# Sheet1.net
KiCad netlist of a schematic drawn in Altium Designer
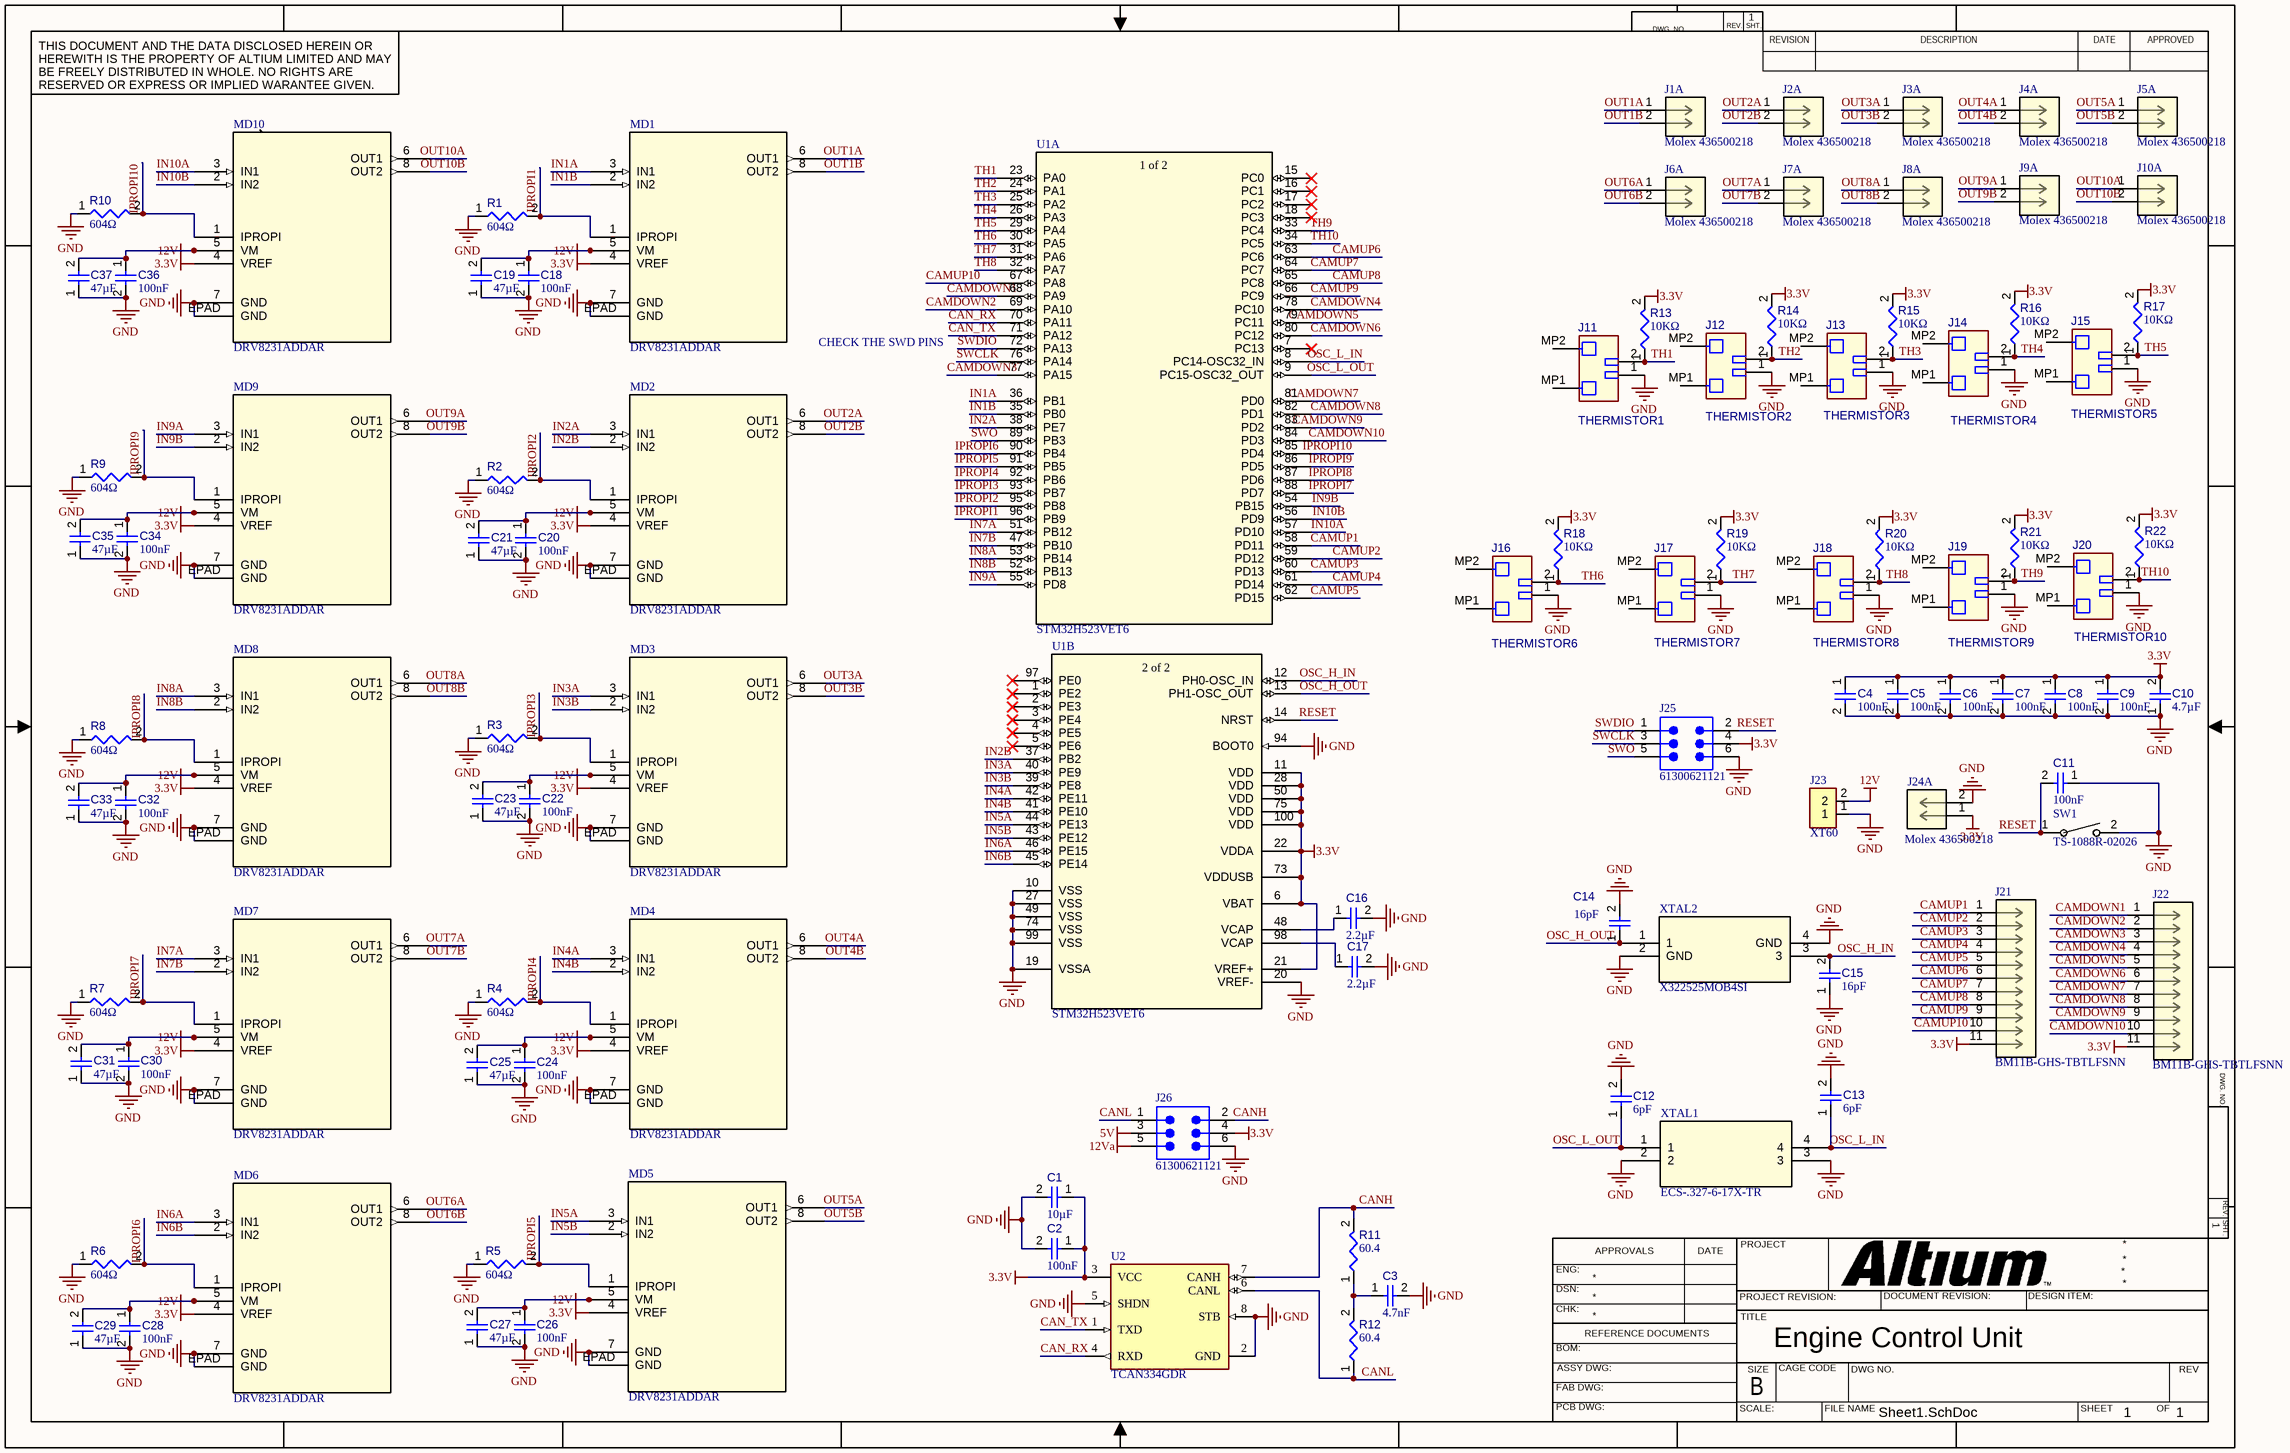
[diagram p0: Sheet1.SchDoc]

(export (version "E")
  (design (tool "Eeschema 10.0.6"))
  (components
    (comp (ref "C1")
      (value "10µF")
      (footprint "CAPC0805(2012)145_L")
      (description "Chip Capacitor, 10µF +/-20%, 25V, 0805, Thickness 1.45 mm")
      (fields (field (name "TOLERANCE") "10%") (field (name "Comment") "Capacitor 10µF +/-20% 25V 0805"))
      (libsource (lib "Caden Chan") (part "CAP-NP-2"))
    )
    (comp (ref "C2")
      (value "100nF")
      (footprint "CAPC0402(1005)60_L")
      (description "Chip Capacitor, 100nF +/-20%, 50V, 0402, Thickness 0.6 mm")
      (fields (field (name "TOLERANCE") "10%") (field (name "Comment") "Capacitor 100nF +/-20% 50V 0402"))
      (libsource (lib "Caden Chan") (part "CAP-NP-2"))
    )
    (comp (ref "C3")
      (value "4.7nF")
      (footprint "CAPC1709X04N")
      (fields (field (name "Comment") "yageo CC0603KRX7R9BB472"))
      (libsource (lib "Caden Chan") (part "CAP-NP-2"))
    )
    (comp (ref "C4")
      (value "100nF")
      (footprint "CAPC0402(1005)60_L")
      (description "Chip Capacitor, 100nF +/-20%, 50V, 0402, Thickness 0.6 mm")
      (fields (field (name "TOLERANCE") "10%") (field (name "Comment") "Capacitor 100nF +/-20% 50V 0402"))
      (libsource (lib "Caden Chan") (part "CAP-NP-2"))
    )
    (comp (ref "C5")
      (value "100nF")
      (footprint "CAPC0402(1005)60_L")
      (description "Chip Capacitor, 100nF +/-20%, 50V, 0402, Thickness 0.6 mm")
      (fields (field (name "TOLERANCE") "10%") (field (name "Comment") "Capacitor 100nF +/-20% 50V 0402"))
      (libsource (lib "Caden Chan") (part "CAP-NP-2"))
    )
    (comp (ref "C6")
      (value "100nF")
      (footprint "CAPC0402(1005)60_L")
      (description "Chip Capacitor, 100nF +/-20%, 50V, 0402, Thickness 0.6 mm")
      (fields (field (name "TOLERANCE") "10%") (field (name "Comment") "Capacitor 100nF +/-20% 50V 0402"))
      (libsource (lib "Caden Chan") (part "CAP-NP-2"))
    )
    (comp (ref "C7")
      (value "100nF")
      (footprint "CAPC0402(1005)60_L")
      (description "Chip Capacitor, 100nF +/-20%, 50V, 0402, Thickness 0.6 mm")
      (fields (field (name "TOLERANCE") "10%") (field (name "Comment") "Capacitor 100nF +/-20% 50V 0402"))
      (libsource (lib "Caden Chan") (part "CAP-NP-2"))
    )
    (comp (ref "C8")
      (value "100nF")
      (footprint "CAPC0402(1005)60_L")
      (description "Chip Capacitor, 100nF +/-20%, 50V, 0402, Thickness 0.6 mm")
      (fields (field (name "TOLERANCE") "10%") (field (name "Comment") "Capacitor 100nF +/-20% 50V 0402"))
      (libsource (lib "Caden Chan") (part "CAP-NP-2"))
    )
    (comp (ref "C9")
      (value "100nF")
      (footprint "CAPC0402(1005)60_L")
      (description "Chip Capacitor, 100nF +/-20%, 50V, 0402, Thickness 0.6 mm")
      (fields (field (name "TOLERANCE") "10%") (field (name "Comment") "Capacitor 100nF +/-20% 50V 0402"))
      (libsource (lib "Caden Chan") (part "CAP-NP-2"))
    )
    (comp (ref "C10")
      (value "4.7µF")
      (footprint "CAPC0603(1608)100_L")
      (description "Chip Capacitor, 4.7µF +/-20%, 10V, 0603, Thickness 1 mm")
      (fields (field (name "TOLERANCE") "10%") (field (name "Comment") "Capacitor 4.7µF +/-20% 10V 0603"))
      (libsource (lib "Caden Chan") (part "CAP-NP-2"))
    )
    (comp (ref "C11")
      (value "100nF")
      (footprint "CAPC0402(1005)60_L")
      (description "Chip Capacitor, 100nF +/-20%, 50V, 0402, Thickness 0.6 mm")
      (fields (field (name "TOLERANCE") "10%") (field (name "Comment") "Capacitor 100nF +/-20% 50V 0402"))
      (libsource (lib "Caden Chan") (part "CAP-NP-2"))
    )
    (comp (ref "C12")
      (value "6pF")
      (footprint "CAPC1709X04N")
      (fields (field (name "Comment") "Yageo CC0603CRNPO9BN6R0"))
      (libsource (lib "Caden Chan") (part "CAP-NP-2"))
    )
    (comp (ref "C13")
      (value "6pF")
      (footprint "CAPC1709X04N")
      (fields (field (name "Comment") "Yageo CC0603CRNPO9BN6R0"))
      (libsource (lib "Caden Chan") (part "CAP-NP-2"))
    )
    (comp (ref "C14")
      (value "16pF")
      (footprint "CAPC1709X04N")
      (description "Multilayer Ceramic Capacitor, 16 pF, 50 V, ± 5%, C0G (NP0), 0603 [1608 Metric]")
      (fields (field (name "Comment") "Yageo CC0603JRNPO9BN160"))
      (libsource (lib "Caden Chan") (part "CAP-NP-2"))
    )
    (comp (ref "C15")
      (value "16pF")
      (footprint "CAPC1709X04N")
      (description "Multilayer Ceramic Capacitor, 16 pF, 50 V, ± 5%, C0G (NP0), 0603 [1608 Metric]")
      (fields (field (name "Comment") "Yageo CC0603JRNPO9BN160"))
      (libsource (lib "Caden Chan") (part "CAP-NP-2"))
    )
    (comp (ref "C16")
      (value "2.2µF")
      (footprint "CAPC1709X04N")
      (fields (field (name "Comment") "yageo CC0603KRX5R8BB225"))
      (libsource (lib "Caden Chan") (part "CAP-NP-2"))
    )
    (comp (ref "C17")
      (value "2.2µF")
      (footprint "CAPC1709X04N")
      (fields (field (name "Comment") "yageo CC0603KRX5R8BB225"))
      (libsource (lib "Caden Chan") (part "CAP-NP-2"))
    )
    (comp (ref "C18")
      (value "100nF")
      (footprint "CAPC0402(1005)60_L")
      (description "Chip Capacitor, 100nF +/-20%, 50V, 0402, Thickness 0.6 mm")
      (fields (field (name "TOLERANCE") "10%") (field (name "Comment") "Capacitor 100nF +/-20% 50V 0402"))
      (libsource (lib "Caden Chan") (part "CAP-NP-2"))
    )
    (comp (ref "C19")
      (value "47µF")
      (footprint "N18F1D473MQ0T0S0N0-Footprint-1")
      (description "±20% 47nF Y5V 1kV Plugin, P=10mm Through Hole Ceramic Capacitors ROHS")
      (fields (field (name "Comment") "N18F1D473MQ0T0S0N0"))
      (libsource (lib "Caden Chan") (part "CAP-NP-2"))
    )
    (comp (ref "C20")
      (value "100nF")
      (footprint "CAPC0402(1005)60_L")
      (description "Chip Capacitor, 100nF +/-20%, 50V, 0402, Thickness 0.6 mm")
      (fields (field (name "TOLERANCE") "10%") (field (name "Comment") "Capacitor 100nF +/-20% 50V 0402"))
      (libsource (lib "Caden Chan") (part "CAP-NP-2"))
    )
    (comp (ref "C21")
      (value "47µF")
      (footprint "N18F1D473MQ0T0S0N0-Footprint-1")
      (description "±20% 47nF Y5V 1kV Plugin, P=10mm Through Hole Ceramic Capacitors ROHS")
      (fields (field (name "Comment") "N18F1D473MQ0T0S0N0"))
      (libsource (lib "Caden Chan") (part "CAP-NP-2"))
    )
    (comp (ref "C22")
      (value "100nF")
      (footprint "CAPC0402(1005)60_L")
      (description "Chip Capacitor, 100nF +/-20%, 50V, 0402, Thickness 0.6 mm")
      (fields (field (name "TOLERANCE") "10%") (field (name "Comment") "Capacitor 100nF +/-20% 50V 0402"))
      (libsource (lib "Caden Chan") (part "CAP-NP-2"))
    )
    (comp (ref "C23")
      (value "47µF")
      (footprint "N18F1D473MQ0T0S0N0-Footprint-1")
      (description "±20% 47nF Y5V 1kV Plugin, P=10mm Through Hole Ceramic Capacitors ROHS")
      (fields (field (name "Comment") "N18F1D473MQ0T0S0N0"))
      (libsource (lib "Caden Chan") (part "CAP-NP-2"))
    )
    (comp (ref "C24")
      (value "100nF")
      (footprint "CAPC0402(1005)60_L")
      (description "Chip Capacitor, 100nF +/-20%, 50V, 0402, Thickness 0.6 mm")
      (fields (field (name "TOLERANCE") "10%") (field (name "Comment") "Capacitor 100nF +/-20% 50V 0402"))
      (libsource (lib "Caden Chan") (part "CAP-NP-2"))
    )
    (comp (ref "C25")
      (value "47µF")
      (footprint "N18F1D473MQ0T0S0N0-Footprint-1")
      (description "±20% 47nF Y5V 1kV Plugin, P=10mm Through Hole Ceramic Capacitors ROHS")
      (fields (field (name "Comment") "N18F1D473MQ0T0S0N0"))
      (libsource (lib "Caden Chan") (part "CAP-NP-2"))
    )
    (comp (ref "C26")
      (value "100nF")
      (footprint "CAPC0402(1005)60_L")
      (description "Chip Capacitor, 100nF +/-20%, 50V, 0402, Thickness 0.6 mm")
      (fields (field (name "TOLERANCE") "10%") (field (name "Comment") "Capacitor 100nF +/-20% 50V 0402"))
      (libsource (lib "Caden Chan") (part "CAP-NP-2"))
    )
    (comp (ref "C27")
      (value "47µF")
      (footprint "N18F1D473MQ0T0S0N0-Footprint-1")
      (description "±20% 47nF Y5V 1kV Plugin, P=10mm Through Hole Ceramic Capacitors ROHS")
      (fields (field (name "Comment") "N18F1D473MQ0T0S0N0"))
      (libsource (lib "Caden Chan") (part "CAP-NP-2"))
    )
    (comp (ref "C28")
      (value "100nF")
      (footprint "CAPC0402(1005)60_L")
      (description "Chip Capacitor, 100nF +/-20%, 50V, 0402, Thickness 0.6 mm")
      (fields (field (name "TOLERANCE") "10%") (field (name "Comment") "Capacitor 100nF +/-20% 50V 0402"))
      (libsource (lib "Caden Chan") (part "CAP-NP-2"))
    )
    (comp (ref "C29")
      (value "47µF")
      (footprint "N18F1D473MQ0T0S0N0-Footprint-1")
      (description "±20% 47nF Y5V 1kV Plugin, P=10mm Through Hole Ceramic Capacitors ROHS")
      (fields (field (name "Comment") "N18F1D473MQ0T0S0N0"))
      (libsource (lib "Caden Chan") (part "CAP-NP-2"))
    )
    (comp (ref "C30")
      (value "100nF")
      (footprint "CAPC0402(1005)60_L")
      (description "Chip Capacitor, 100nF +/-20%, 50V, 0402, Thickness 0.6 mm")
      (fields (field (name "TOLERANCE") "10%") (field (name "Comment") "Capacitor 100nF +/-20% 50V 0402"))
      (libsource (lib "Caden Chan") (part "CAP-NP-2"))
    )
    (comp (ref "C31")
      (value "47µF")
      (footprint "N18F1D473MQ0T0S0N0-Footprint-1")
      (description "±20% 47nF Y5V 1kV Plugin, P=10mm Through Hole Ceramic Capacitors ROHS")
      (fields (field (name "Comment") "N18F1D473MQ0T0S0N0"))
      (libsource (lib "Caden Chan") (part "CAP-NP-2"))
    )
    (comp (ref "C32")
      (value "100nF")
      (footprint "CAPC0402(1005)60_L")
      (description "Chip Capacitor, 100nF +/-20%, 50V, 0402, Thickness 0.6 mm")
      (fields (field (name "TOLERANCE") "10%") (field (name "Comment") "Capacitor 100nF +/-20% 50V 0402"))
      (libsource (lib "Caden Chan") (part "CAP-NP-2"))
    )
    (comp (ref "C33")
      (value "47µF")
      (footprint "N18F1D473MQ0T0S0N0-Footprint-1")
      (description "±20% 47nF Y5V 1kV Plugin, P=10mm Through Hole Ceramic Capacitors ROHS")
      (fields (field (name "Comment") "N18F1D473MQ0T0S0N0"))
      (libsource (lib "Caden Chan") (part "CAP-NP-2"))
    )
    (comp (ref "C34")
      (value "100nF")
      (footprint "CAPC0402(1005)60_L")
      (description "Chip Capacitor, 100nF +/-20%, 50V, 0402, Thickness 0.6 mm")
      (fields (field (name "TOLERANCE") "10%") (field (name "Comment") "Capacitor 100nF +/-20% 50V 0402"))
      (libsource (lib "Caden Chan") (part "CAP-NP-2"))
    )
    (comp (ref "C35")
      (value "47µF")
      (footprint "N18F1D473MQ0T0S0N0-Footprint-1")
      (description "±20% 47nF Y5V 1kV Plugin, P=10mm Through Hole Ceramic Capacitors ROHS")
      (fields (field (name "Comment") "N18F1D473MQ0T0S0N0"))
      (libsource (lib "Caden Chan") (part "CAP-NP-2"))
    )
    (comp (ref "C36")
      (value "100nF")
      (footprint "CAPC0402(1005)60_L")
      (description "Chip Capacitor, 100nF +/-20%, 50V, 0402, Thickness 0.6 mm")
      (fields (field (name "TOLERANCE") "10%") (field (name "Comment") "Capacitor 100nF +/-20% 50V 0402"))
      (libsource (lib "Caden Chan") (part "CAP-NP-2"))
    )
    (comp (ref "C37")
      (value "47µF")
      (footprint "N18F1D473MQ0T0S0N0-Footprint-1")
      (description "±20% 47nF Y5V 1kV Plugin, P=10mm Through Hole Ceramic Capacitors ROHS")
      (fields (field (name "Comment") "N18F1D473MQ0T0S0N0"))
      (libsource (lib "Caden Chan") (part "CAP-NP-2"))
    )
    (comp (ref "J1")
      (value "Molex 436500218")
      (footprint "CONN_SD-43650-007_02_MOL")
      (description "No Description Available")
      (libsource (lib "") (part "436500218_1"))
    )
    (comp (ref "J2")
      (value "Molex 436500218")
      (footprint "CONN_SD-43650-007_02_MOL")
      (description "No Description Available")
      (libsource (lib "") (part "436500218_1"))
    )
    (comp (ref "J3")
      (value "Molex 436500218")
      (footprint "CONN_SD-43650-007_02_MOL")
      (description "No Description Available")
      (libsource (lib "") (part "436500218_1"))
    )
    (comp (ref "J4")
      (value "Molex 436500218")
      (footprint "CONN_SD-43650-007_02_MOL")
      (description "No Description Available")
      (libsource (lib "") (part "436500218_1"))
    )
    (comp (ref "J5")
      (value "Molex 436500218")
      (footprint "CONN_SD-43650-007_02_MOL")
      (description "No Description Available")
      (libsource (lib "") (part "436500218_1"))
    )
    (comp (ref "J6")
      (value "Molex 436500218")
      (footprint "CONN_SD-43650-007_02_MOL")
      (description "No Description Available")
      (libsource (lib "") (part "436500218_1"))
    )
    (comp (ref "J7")
      (value "Molex 436500218")
      (footprint "CONN_SD-43650-007_02_MOL")
      (description "No Description Available")
      (libsource (lib "") (part "436500218_1"))
    )
    (comp (ref "J8")
      (value "Molex 436500218")
      (footprint "CONN_SD-43650-007_02_MOL")
      (description "No Description Available")
      (libsource (lib "") (part "436500218_1"))
    )
    (comp (ref "J9")
      (value "Molex 436500218")
      (footprint "CONN_SD-43650-007_02_MOL")
      (description "No Description Available")
      (libsource (lib "") (part "436500218_1"))
    )
    (comp (ref "J10")
      (value "Molex 436500218")
      (footprint "CONN_SD-43650-007_02_MOL")
      (description "No Description Available")
      (libsource (lib "") (part "436500218_1"))
    )
    (comp (ref "J11")
      (value "THERMISTOR1")
      (footprint "JST-BM02B-GHS-TBT_V")
      (libsource (lib "Caden Chan") (part "CMP-00144-3"))
    )
    (comp (ref "J12")
      (value "THERMISTOR2")
      (footprint "JST-BM02B-GHS-TBT_V")
      (libsource (lib "Caden Chan") (part "CMP-00144-3"))
    )
    (comp (ref "J13")
      (value "THERMISTOR3")
      (footprint "JST-BM02B-GHS-TBT_V")
      (libsource (lib "Caden Chan") (part "CMP-00144-3"))
    )
    (comp (ref "J14")
      (value "THERMISTOR4")
      (footprint "JST-BM02B-GHS-TBT_V")
      (libsource (lib "Caden Chan") (part "CMP-00144-3"))
    )
    (comp (ref "J15")
      (value "THERMISTOR5")
      (footprint "JST-BM02B-GHS-TBT_V")
      (libsource (lib "Caden Chan") (part "CMP-00144-3"))
    )
    (comp (ref "J16")
      (value "THERMISTOR6")
      (footprint "JST-BM02B-GHS-TBT_V")
      (libsource (lib "Caden Chan") (part "CMP-00144-3"))
    )
    (comp (ref "J17")
      (value "THERMISTOR7")
      (footprint "JST-BM02B-GHS-TBT_V")
      (libsource (lib "Caden Chan") (part "CMP-00144-3"))
    )
    (comp (ref "J18")
      (value "THERMISTOR8")
      (footprint "JST-BM02B-GHS-TBT_V")
      (libsource (lib "Caden Chan") (part "CMP-00144-3"))
    )
    (comp (ref "J19")
      (value "THERMISTOR9")
      (footprint "JST-BM02B-GHS-TBT_V")
      (libsource (lib "Caden Chan") (part "CMP-00144-3"))
    )
    (comp (ref "J20")
      (value "THERMISTOR10")
      (footprint "JST-BM02B-GHS-TBT_V")
      (libsource (lib "Caden Chan") (part "CMP-00144-3"))
    )
    (comp (ref "J21")
      (value "BM11B-GHS-TBTLFSNN")
      (footprint "CONN11_BM11B-GHS-TBTLFSNN_JST")
      (description "No Description Available")
      (fields
        (field (name "MANUFACTURER_PART_NUMBER") "BM11B-GHS-TBT(LF)(SN)(N)")
        (field (name "COPYRIGHT") "Copyright (C) 2025 Ultra Librarian. All rights reserved.")
      )
      (libsource (lib "Caden Chan") (part "BM11B-GHS-TBTLFSNN"))
    )
    (comp (ref "J22")
      (value "BM11B-GHS-TBTLFSNN")
      (footprint "CONN11_BM11B-GHS-TBTLFSNN_JST")
      (description "No Description Available")
      (fields
        (field (name "MANUFACTURER_PART_NUMBER") "BM11B-GHS-TBT(LF)(SN)(N)")
        (field (name "COPYRIGHT") "Copyright (C) 2025 Ultra Librarian. All rights reserved.")
      )
      (libsource (lib "Caden Chan") (part "BM11B-GHS-TBTLFSNN"))
    )
    (comp (ref "J23")
      (value "XT60")
      (footprint "AMASS_XT60PB-M")
      (description "Power connector; 65A; PIN: 2; Colour: yellow")
      (fields (field (name "MF") "Pololu") (field (name "MP") "XT60 YELLOW"))
      (libsource (lib "Caden Chan") (part "XT60_YELLOW"))
    )
    (comp (ref "J24")
      (value "Molex 436500218")
      (footprint "CONN_SD-43650-007_02_MOL")
      (description "No Description Available")
      (libsource (lib "Caden Chan") (part "436500218"))
    )
    (comp (ref "J25")
      (value "61300621121")
      (footprint "61300621121")
      (description "WR-PHD Pin Header, THT, Vertical, pitch 2.54mm, 2 Row, 6P")
      (fields (field (name "MANUFACTURER") "Wurth Elektronik"))
      (libsource (lib "Caden Chan") (part "61300621121"))
    )
    (comp (ref "J26")
      (value "61300621121")
      (footprint "61300621121")
      (description "WR-PHD Pin Header, THT, Vertical, pitch 2.54mm, 2 Row, 6P")
      (fields (field (name "MANUFACTURER") "Wurth Elektronik"))
      (libsource (lib "Caden Chan") (part "61300621121"))
    )
    (comp (ref "MD1")
      (value "DRV8231ADDAR")
      (footprint "SOIC-8-DDA-DRV8231_TEX")
      (description "No Description Available")
      (libsource (lib "Caden Chan") (part "DRV8231ADDAR"))
    )
    (comp (ref "MD2")
      (value "DRV8231ADDAR")
      (footprint "SOIC-8-DDA-DRV8231_TEX")
      (description "No Description Available")
      (libsource (lib "Caden Chan") (part "DRV8231ADDAR"))
    )
    (comp (ref "MD3")
      (value "DRV8231ADDAR")
      (footprint "SOIC-8-DDA-DRV8231_TEX")
      (description "No Description Available")
      (libsource (lib "Caden Chan") (part "DRV8231ADDAR"))
    )
    (comp (ref "MD4")
      (value "DRV8231ADDAR")
      (footprint "SOIC-8-DDA-DRV8231_TEX")
      (description "No Description Available")
      (libsource (lib "Caden Chan") (part "DRV8231ADDAR"))
    )
    (comp (ref "MD5")
      (value "DRV8231ADDAR")
      (footprint "SOIC-8-DDA-DRV8231_TEX")
      (description "No Description Available")
      (libsource (lib "Caden Chan") (part "DRV8231ADDAR"))
    )
    (comp (ref "MD6")
      (value "DRV8231ADDAR")
      (footprint "SOIC-8-DDA-DRV8231_TEX")
      (description "No Description Available")
      (libsource (lib "Caden Chan") (part "DRV8231ADDAR"))
    )
    (comp (ref "MD7")
      (value "DRV8231ADDAR")
      (footprint "SOIC-8-DDA-DRV8231_TEX")
      (description "No Description Available")
      (libsource (lib "Caden Chan") (part "DRV8231ADDAR"))
    )
    (comp (ref "MD8")
      (value "DRV8231ADDAR")
      (footprint "SOIC-8-DDA-DRV8231_TEX")
      (description "No Description Available")
      (libsource (lib "Caden Chan") (part "DRV8231ADDAR"))
    )
    (comp (ref "MD9")
      (value "DRV8231ADDAR")
      (footprint "SOIC-8-DDA-DRV8231_TEX")
      (description "No Description Available")
      (libsource (lib "Caden Chan") (part "DRV8231ADDAR"))
    )
    (comp (ref "MD10")
      (value "DRV8231ADDAR")
      (footprint "SOIC-8-DDA-DRV8231_TEX")
      (description "No Description Available")
      (libsource (lib "Caden Chan") (part "DRV8231ADDAR"))
    )
    (comp (ref "R1")
      (value "604Ω")
      (footprint "RESC2013X50X35ML15T15")
      (description "Chip Resistor, 10 KOhm, +/- 1%, 125 mW, -55 to 155 degC, 0805 (2012 Metric)")
      (fields (field (name "TOLERANCE") "1%") (field (name "POWER") "125mW"))
      (libsource (lib "Caden Chan") (part "RES-2"))
    )
    (comp (ref "R2")
      (value "604Ω")
      (footprint "RESC2013X50X35ML15T15")
      (description "Chip Resistor, 10 KOhm, +/- 1%, 125 mW, -55 to 155 degC, 0805 (2012 Metric)")
      (fields (field (name "TOLERANCE") "1%") (field (name "POWER") "125mW"))
      (libsource (lib "Caden Chan") (part "RES-2"))
    )
    (comp (ref "R3")
      (value "604Ω")
      (footprint "RESC2013X50X35ML15T15")
      (description "Chip Resistor, 10 KOhm, +/- 1%, 125 mW, -55 to 155 degC, 0805 (2012 Metric)")
      (fields (field (name "TOLERANCE") "1%") (field (name "POWER") "125mW"))
      (libsource (lib "Caden Chan") (part "RES-2"))
    )
    (comp (ref "R4")
      (value "604Ω")
      (footprint "RESC2013X50X35ML15T15")
      (description "Chip Resistor, 10 KOhm, +/- 1%, 125 mW, -55 to 155 degC, 0805 (2012 Metric)")
      (fields (field (name "TOLERANCE") "1%") (field (name "POWER") "125mW"))
      (libsource (lib "Caden Chan") (part "RES-2"))
    )
    (comp (ref "R5")
      (value "604Ω")
      (footprint "RESC2013X50X35ML15T15")
      (description "Chip Resistor, 10 KOhm, +/- 1%, 125 mW, -55 to 155 degC, 0805 (2012 Metric)")
      (fields (field (name "TOLERANCE") "1%") (field (name "POWER") "125mW"))
      (libsource (lib "Caden Chan") (part "RES-2"))
    )
    (comp (ref "R6")
      (value "604Ω")
      (footprint "RESC2013X50X35ML15T15")
      (description "Chip Resistor, 10 KOhm, +/- 1%, 125 mW, -55 to 155 degC, 0805 (2012 Metric)")
      (fields (field (name "TOLERANCE") "1%") (field (name "POWER") "125mW"))
      (libsource (lib "Caden Chan") (part "RES-2"))
    )
    (comp (ref "R7")
      (value "604Ω")
      (footprint "RESC2013X50X35ML15T15")
      (description "Chip Resistor, 10 KOhm, +/- 1%, 125 mW, -55 to 155 degC, 0805 (2012 Metric)")
      (fields (field (name "TOLERANCE") "1%") (field (name "POWER") "125mW"))
      (libsource (lib "Caden Chan") (part "RES-2"))
    )
    (comp (ref "R8")
      (value "604Ω")
      (footprint "RESC2013X50X35ML15T15")
      (description "Chip Resistor, 10 KOhm, +/- 1%, 125 mW, -55 to 155 degC, 0805 (2012 Metric)")
      (fields (field (name "TOLERANCE") "1%") (field (name "POWER") "125mW"))
      (libsource (lib "Caden Chan") (part "RES-2"))
    )
    (comp (ref "R9")
      (value "604Ω")
      (footprint "RESC2013X50X35ML15T15")
      (description "Chip Resistor, 10 KOhm, +/- 1%, 125 mW, -55 to 155 degC, 0805 (2012 Metric)")
      (fields (field (name "TOLERANCE") "1%") (field (name "POWER") "125mW"))
      (libsource (lib "Caden Chan") (part "RES-2"))
    )
    (comp (ref "R10")
      (value "604Ω")
      (footprint "RESC2013X50X35ML15T15")
      (description "Chip Resistor, 10 KOhm, +/- 1%, 125 mW, -55 to 155 degC, 0805 (2012 Metric)")
      (fields (field (name "TOLERANCE") "1%") (field (name "POWER") "125mW"))
      (libsource (lib "Caden Chan") (part "RES-2"))
    )
    (comp (ref "R11")
      (value "60.4")
      (footprint "RESC1709X04N")
      (fields
        (field (name "TOLERANCE") "1%")
        (field (name "POWER") "100mW")
        (field (name "Comment") "yageo RC0603FR-0760R4L")
      )
      (libsource (lib "Caden Chan") (part "RES-2"))
    )
    (comp (ref "R12")
      (value "60.4")
      (footprint "RESC1709X04N")
      (fields
        (field (name "TOLERANCE") "1%")
        (field (name "POWER") "100mW")
        (field (name "Comment") "yageo RC0603FR-0760R4L")
      )
      (libsource (lib "Caden Chan") (part "RES-2"))
    )
    (comp (ref "R13")
      (value "10KΩ")
      (footprint "RESC0402(1005)_L")
      (description "10R 0.063W 1% 0402 (1005 Metric)  SMD")
      (fields (field (name "TOLERANCE") "1%") (field (name "POWER") "63mW"))
      (libsource (lib "Caden Chan") (part "10R2F"))
    )
    (comp (ref "R14")
      (value "10KΩ")
      (footprint "RESC0402(1005)_L")
      (description "10R 0.063W 1% 0402 (1005 Metric)  SMD")
      (fields (field (name "TOLERANCE") "1%") (field (name "POWER") "63mW"))
      (libsource (lib "Caden Chan") (part "10R2F"))
    )
    (comp (ref "R15")
      (value "10KΩ")
      (footprint "RESC0402(1005)_L")
      (description "10R 0.063W 1% 0402 (1005 Metric)  SMD")
      (fields (field (name "TOLERANCE") "1%") (field (name "POWER") "63mW"))
      (libsource (lib "Caden Chan") (part "10R2F"))
    )
    (comp (ref "R16")
      (value "10KΩ")
      (footprint "RESC0402(1005)_L")
      (description "10R 0.063W 1% 0402 (1005 Metric)  SMD")
      (fields (field (name "TOLERANCE") "1%") (field (name "POWER") "63mW"))
      (libsource (lib "Caden Chan") (part "10R2F"))
    )
    (comp (ref "R17")
      (value "10KΩ")
      (footprint "RESC0402(1005)_L")
      (description "10R 0.063W 1% 0402 (1005 Metric)  SMD")
      (fields (field (name "TOLERANCE") "1%") (field (name "POWER") "63mW"))
      (libsource (lib "Caden Chan") (part "10R2F"))
    )
    (comp (ref "R18")
      (value "10KΩ")
      (footprint "RESC0402(1005)_L")
      (description "10R 0.063W 1% 0402 (1005 Metric)  SMD")
      (fields (field (name "TOLERANCE") "1%") (field (name "POWER") "63mW"))
      (libsource (lib "Caden Chan") (part "10R2F"))
    )
    (comp (ref "R19")
      (value "10KΩ")
      (footprint "RESC0402(1005)_L")
      (description "10R 0.063W 1% 0402 (1005 Metric)  SMD")
      (fields (field (name "TOLERANCE") "1%") (field (name "POWER") "63mW"))
      (libsource (lib "Caden Chan") (part "10R2F"))
    )
    (comp (ref "R20")
      (value "10KΩ")
      (footprint "RESC0402(1005)_L")
      (description "10R 0.063W 1% 0402 (1005 Metric)  SMD")
      (fields (field (name "TOLERANCE") "1%") (field (name "POWER") "63mW"))
      (libsource (lib "Caden Chan") (part "10R2F"))
    )
    (comp (ref "R21")
      (value "10KΩ")
      (footprint "RESC0402(1005)_L")
      (description "10R 0.063W 1% 0402 (1005 Metric)  SMD")
      (fields (field (name "TOLERANCE") "1%") (field (name "POWER") "63mW"))
      (libsource (lib "Caden Chan") (part "10R2F"))
    )
    (comp (ref "R22")
      (value "10KΩ")
      (footprint "RESC0402(1005)_L")
      (description "10R 0.063W 1% 0402 (1005 Metric)  SMD")
      (fields (field (name "TOLERANCE") "1%") (field (name "POWER") "63mW"))
      (libsource (lib "Caden Chan") (part "10R2F"))
    )
    (comp (ref "SW1")
      (value "TS-1088R-02026")
      (footprint "SW_TS-1088R-02026_XNP")
      (description "No Description Available")
      (fields (field (name "COPYRIGHT") "Copyright (C) 2025 Ultra Librarian. All rights reserved."))
      (libsource (lib "Caden Chan") (part "TS-1088R-02026"))
    )
    (comp (ref "U1")
      (value "STM32H523VET6")
      (footprint "LQFP-100")
      (description "No Description Available")
      (libsource (lib "") (part "STM32H523VET6_1"))
    )
    (comp (ref "U2")
      (value "TCAN334GDR")
      (footprint "FP-D0008A-IPC_B")
      (description "Interface Circuit, PDSO8")
      (libsource (lib "Caden Chan") (part "5621f34e3963f16c2984a53bd88c479"))
    )
    (comp (ref "XTAL1")
      (value "ECS-.327-6-17X-TR")
      (footprint "XTAL_7X-TR_ECS")
      (description "No Description Available")
      (fields (field (name "COPYRIGHT") "Copyright (C) 2025 Ultra Librarian. All rights reserved."))
      (libsource (lib "Caden Chan") (part "ECS-.327-6-17X-TR"))
    )
    (comp (ref "XTAL2")
      (value "X322525MOB4SI")
      (footprint "SMT_MOB4SI_YXC")
      (description "No Description Available")
      (fields (field (name "COPYRIGHT") "Copyright (C) 2025 Ultra Librarian. All rights reserved."))
      (libsource (lib "Caden Chan") (part "X322525MOB4SI"))
    )
  )
  (nets
    (net (code "1") (name "/CAMDOWN1") (class "Default")
      (node (ref "J22") (pin "1") (pinfunction "1_1") (pintype "passive"))
      (node (ref "U1") (pin "68") (pinfunction "PA9_68") (pintype "bidirectional"))
    )
    (net (code "2") (name "/CAMDOWN2") (class "Default")
      (node (ref "J22") (pin "2") (pinfunction "2_2") (pintype "passive"))
      (node (ref "U1") (pin "69") (pinfunction "PA10_69") (pintype "bidirectional"))
    )
    (net (code "3") (name "/CAMDOWN3") (class "Default")
      (node (ref "J22") (pin "3") (pinfunction "3_3") (pintype "passive"))
      (node (ref "U1") (pin "77") (pinfunction "PA15_77") (pintype "bidirectional"))
    )
    (net (code "4") (name "/CAMDOWN4") (class "Default")
      (node (ref "J22") (pin "4") (pinfunction "4_4") (pintype "passive"))
      (node (ref "U1") (pin "78") (pinfunction "PC10_78") (pintype "bidirectional"))
    )
    (net (code "5") (name "/CAMDOWN5") (class "Default")
      (node (ref "J22") (pin "5") (pinfunction "5_5") (pintype "passive"))
      (node (ref "U1") (pin "79") (pinfunction "PC11_79") (pintype "bidirectional"))
    )
    (net (code "6") (name "/CAMDOWN6") (class "Default")
      (node (ref "J22") (pin "6") (pinfunction "6_6") (pintype "passive"))
      (node (ref "U1") (pin "80") (pinfunction "PC12_80") (pintype "bidirectional"))
    )
    (net (code "7") (name "/CAMDOWN7") (class "Default")
      (node (ref "J22") (pin "7") (pinfunction "7_7") (pintype "passive"))
      (node (ref "U1") (pin "81") (pinfunction "PD0_81") (pintype "bidirectional"))
    )
    (net (code "8") (name "/CAMDOWN8") (class "Default")
      (node (ref "J22") (pin "8") (pinfunction "8_8") (pintype "passive"))
      (node (ref "U1") (pin "82") (pinfunction "PD1_82") (pintype "bidirectional"))
    )
    (net (code "9") (name "/CAMDOWN9") (class "Default")
      (node (ref "J22") (pin "9") (pinfunction "9_9") (pintype "passive"))
      (node (ref "U1") (pin "83") (pinfunction "PD2_83") (pintype "bidirectional"))
    )
    (net (code "10") (name "/CAMDOWN10") (class "Default")
      (node (ref "J22") (pin "10") (pinfunction "10_10") (pintype "passive"))
      (node (ref "U1") (pin "84") (pinfunction "PD3_84") (pintype "bidirectional"))
    )
    (net (code "11") (name "/CAMUP1") (class "Default")
      (node (ref "J21") (pin "1") (pinfunction "1_1") (pintype "passive"))
      (node (ref "U1") (pin "58") (pinfunction "PD11_58") (pintype "bidirectional"))
    )
    (net (code "12") (name "/CAMUP2") (class "Default")
      (node (ref "J21") (pin "2") (pinfunction "2_2") (pintype "passive"))
      (node (ref "U1") (pin "59") (pinfunction "PD12_59") (pintype "bidirectional"))
    )
    (net (code "13") (name "/CAMUP3") (class "Default")
      (node (ref "J21") (pin "3") (pinfunction "3_3") (pintype "passive"))
      (node (ref "U1") (pin "60") (pinfunction "PD13_60") (pintype "bidirectional"))
    )
    (net (code "14") (name "/CAMUP4") (class "Default")
      (node (ref "J21") (pin "4") (pinfunction "4_4") (pintype "passive"))
      (node (ref "U1") (pin "61") (pinfunction "PD14_61") (pintype "bidirectional"))
    )
    (net (code "15") (name "/CAMUP5") (class "Default")
      (node (ref "J21") (pin "5") (pinfunction "5_5") (pintype "passive"))
      (node (ref "U1") (pin "62") (pinfunction "PD15_62") (pintype "bidirectional"))
    )
    (net (code "16") (name "/CAMUP6") (class "Default")
      (node (ref "J21") (pin "6") (pinfunction "6_6") (pintype "passive"))
      (node (ref "U1") (pin "63") (pinfunction "PC6_63") (pintype "bidirectional"))
    )
    (net (code "17") (name "/CAMUP7") (class "Default")
      (node (ref "J21") (pin "7") (pinfunction "7_7") (pintype "passive"))
      (node (ref "U1") (pin "64") (pinfunction "PC7_64") (pintype "bidirectional"))
    )
    (net (code "18") (name "/CAMUP8") (class "Default")
      (node (ref "J21") (pin "8") (pinfunction "8_8") (pintype "passive"))
      (node (ref "U1") (pin "65") (pinfunction "PC8_65") (pintype "bidirectional"))
    )
    (net (code "19") (name "/CAMUP9") (class "Default")
      (node (ref "J21") (pin "9") (pinfunction "9_9") (pintype "passive"))
      (node (ref "U1") (pin "66") (pinfunction "PC9_66") (pintype "bidirectional"))
    )
    (net (code "20") (name "/CAMUP10") (class "Default")
      (node (ref "J21") (pin "10") (pinfunction "10_10") (pintype "passive"))
      (node (ref "U1") (pin "67") (pinfunction "PA8_67") (pintype "bidirectional"))
    )
    (net (code "21") (name "/CANH") (class "Default")
      (node (ref "J26") (pin "2") (pinfunction "2_2") (pintype "passive"))
      (node (ref "R11") (pin "2") (pinfunction "2_2") (pintype "passive"))
      (node (ref "U2") (pin "7") (pinfunction "CANH_7") (pintype "bidirectional"))
    )
    (net (code "22") (name "/CANL") (class "Default")
      (node (ref "J26") (pin "1") (pinfunction "1_1") (pintype "passive"))
      (node (ref "R12") (pin "1") (pinfunction "1_1") (pintype "passive"))
      (node (ref "U2") (pin "6") (pinfunction "CANL_6") (pintype "bidirectional"))
    )
    (net (code "23") (name "/CAN_RX") (class "Default")
      (node (ref "U1") (pin "70") (pinfunction "PA11_70") (pintype "bidirectional"))
      (node (ref "U2") (pin "4") (pinfunction "RXD_4") (pintype "output"))
    )
    (net (code "24") (name "/CAN_TX") (class "Default")
      (node (ref "U1") (pin "71") (pinfunction "PA12_71") (pintype "bidirectional"))
      (node (ref "U2") (pin "1") (pinfunction "TXD_1") (pintype "input"))
    )
    (net (code "25") (name "/IN1A") (class "Default")
      (node (ref "MD1") (pin "3") (pinfunction "IN1_3") (pintype "input"))
      (node (ref "U1") (pin "36") (pinfunction "PB1_36") (pintype "bidirectional"))
    )
    (net (code "26") (name "/IN1B") (class "Default")
      (node (ref "MD1") (pin "2") (pinfunction "IN2_2") (pintype "input"))
      (node (ref "U1") (pin "35") (pinfunction "PB0_35") (pintype "bidirectional"))
    )
    (net (code "27") (name "/IN2A") (class "Default")
      (node (ref "MD2") (pin "3") (pinfunction "IN1_3") (pintype "input"))
      (node (ref "U1") (pin "38") (pinfunction "PE7_38") (pintype "bidirectional"))
    )
    (net (code "28") (name "/IN2B") (class "Default")
      (node (ref "MD2") (pin "2") (pinfunction "IN2_2") (pintype "input"))
      (node (ref "U1") (pin "37") (pinfunction "PB2_37") (pintype "bidirectional"))
    )
    (net (code "29") (name "/IN3A") (class "Default")
      (node (ref "MD3") (pin "3") (pinfunction "IN1_3") (pintype "input"))
      (node (ref "U1") (pin "40") (pinfunction "PE9_40") (pintype "bidirectional"))
    )
    (net (code "30") (name "/IN3B") (class "Default")
      (node (ref "MD3") (pin "2") (pinfunction "IN2_2") (pintype "input"))
      (node (ref "U1") (pin "39") (pinfunction "PE8_39") (pintype "bidirectional"))
    )
    (net (code "31") (name "/IN4A") (class "Default")
      (node (ref "MD4") (pin "3") (pinfunction "IN1_3") (pintype "input"))
      (node (ref "U1") (pin "42") (pinfunction "PE11_42") (pintype "bidirectional"))
    )
    (net (code "32") (name "/IN4B") (class "Default")
      (node (ref "MD4") (pin "2") (pinfunction "IN2_2") (pintype "input"))
      (node (ref "U1") (pin "41") (pinfunction "PE10_41") (pintype "bidirectional"))
    )
    (net (code "33") (name "/IN5A") (class "Default")
      (node (ref "MD5") (pin "3") (pinfunction "IN1_3") (pintype "input"))
      (node (ref "U1") (pin "44") (pinfunction "PE13_44") (pintype "bidirectional"))
    )
    (net (code "34") (name "/IN5B") (class "Default")
      (node (ref "MD5") (pin "2") (pinfunction "IN2_2") (pintype "input"))
      (node (ref "U1") (pin "43") (pinfunction "PE12_43") (pintype "bidirectional"))
    )
    (net (code "35") (name "/IN6A") (class "Default")
      (node (ref "MD6") (pin "3") (pinfunction "IN1_3") (pintype "input"))
      (node (ref "U1") (pin "46") (pinfunction "PE15_46") (pintype "bidirectional"))
    )
    (net (code "36") (name "/IN6B") (class "Default")
      (node (ref "MD6") (pin "2") (pinfunction "IN2_2") (pintype "input"))
      (node (ref "U1") (pin "45") (pinfunction "PE14_45") (pintype "bidirectional"))
    )
    (net (code "37") (name "/IN7A") (class "Default")
      (node (ref "MD7") (pin "3") (pinfunction "IN1_3") (pintype "input"))
      (node (ref "U1") (pin "51") (pinfunction "PB12_51") (pintype "bidirectional"))
    )
    (net (code "38") (name "/IN7B") (class "Default")
      (node (ref "MD7") (pin "2") (pinfunction "IN2_2") (pintype "input"))
      (node (ref "U1") (pin "47") (pinfunction "PB10_47") (pintype "bidirectional"))
    )
    (net (code "39") (name "/IN8A") (class "Default")
      (node (ref "MD8") (pin "3") (pinfunction "IN1_3") (pintype "input"))
      (node (ref "U1") (pin "53") (pinfunction "PB14_53") (pintype "bidirectional"))
    )
    (net (code "40") (name "/IN8B") (class "Default")
      (node (ref "MD8") (pin "2") (pinfunction "IN2_2") (pintype "input"))
      (node (ref "U1") (pin "52") (pinfunction "PB13_52") (pintype "bidirectional"))
    )
    (net (code "41") (name "/IN9A") (class "Default")
      (node (ref "MD9") (pin "3") (pinfunction "IN1_3") (pintype "input"))
      (node (ref "U1") (pin "55") (pinfunction "PD8_55") (pintype "bidirectional"))
    )
    (net (code "42") (name "/IN9B") (class "Default")
      (node (ref "MD9") (pin "2") (pinfunction "IN2_2") (pintype "input"))
      (node (ref "U1") (pin "54") (pinfunction "PB15_54") (pintype "bidirectional"))
    )
    (net (code "43") (name "/IN10A") (class "Default")
      (node (ref "MD10") (pin "3") (pinfunction "IN1_3") (pintype "input"))
      (node (ref "U1") (pin "57") (pinfunction "PD10_57") (pintype "bidirectional"))
    )
    (net (code "44") (name "/IN10B") (class "Default")
      (node (ref "MD10") (pin "2") (pinfunction "IN2_2") (pintype "input"))
      (node (ref "U1") (pin "56") (pinfunction "PD9_56") (pintype "bidirectional"))
    )
    (net (code "45") (name "/IPROPI1") (class "Default")
      (node (ref "MD1") (pin "1") (pinfunction "IPROPI_1") (pintype "power_in"))
      (node (ref "R1") (pin "2") (pinfunction "2_2") (pintype "passive"))
      (node (ref "U1") (pin "96") (pinfunction "PB9_96") (pintype "bidirectional"))
    )
    (net (code "46") (name "/IPROPI2") (class "Default")
      (node (ref "MD2") (pin "1") (pinfunction "IPROPI_1") (pintype "power_in"))
      (node (ref "R2") (pin "2") (pinfunction "2_2") (pintype "passive"))
      (node (ref "U1") (pin "95") (pinfunction "PB8_95") (pintype "bidirectional"))
    )
    (net (code "47") (name "/IPROPI3") (class "Default")
      (node (ref "MD3") (pin "1") (pinfunction "IPROPI_1") (pintype "power_in"))
      (node (ref "R3") (pin "2") (pinfunction "2_2") (pintype "passive"))
      (node (ref "U1") (pin "93") (pinfunction "PB7_93") (pintype "bidirectional"))
    )
    (net (code "48") (name "/IPROPI4") (class "Default")
      (node (ref "MD4") (pin "1") (pinfunction "IPROPI_1") (pintype "power_in"))
      (node (ref "R4") (pin "2") (pinfunction "2_2") (pintype "passive"))
      (node (ref "U1") (pin "92") (pinfunction "PB6_92") (pintype "bidirectional"))
    )
    (net (code "49") (name "/IPROPI5") (class "Default")
      (node (ref "MD5") (pin "1") (pinfunction "IPROPI_1") (pintype "power_in"))
      (node (ref "R5") (pin "2") (pinfunction "2_2") (pintype "passive"))
      (node (ref "U1") (pin "91") (pinfunction "PB5_91") (pintype "bidirectional"))
    )
    (net (code "50") (name "/IPROPI6") (class "Default")
      (node (ref "MD6") (pin "1") (pinfunction "IPROPI_1") (pintype "power_in"))
      (node (ref "R6") (pin "2") (pinfunction "2_2") (pintype "passive"))
      (node (ref "U1") (pin "90") (pinfunction "PB4_90") (pintype "bidirectional"))
    )
    (net (code "51") (name "/IPROPI7") (class "Default")
      (node (ref "MD7") (pin "1") (pinfunction "IPROPI_1") (pintype "power_in"))
      (node (ref "R7") (pin "2") (pinfunction "2_2") (pintype "passive"))
      (node (ref "U1") (pin "88") (pinfunction "PD7_88") (pintype "bidirectional"))
    )
    (net (code "52") (name "/IPROPI8") (class "Default")
      (node (ref "MD8") (pin "1") (pinfunction "IPROPI_1") (pintype "power_in"))
      (node (ref "R8") (pin "2") (pinfunction "2_2") (pintype "passive"))
      (node (ref "U1") (pin "87") (pinfunction "PD6_87") (pintype "bidirectional"))
    )
    (net (code "53") (name "/IPROPI9") (class "Default")
      (node (ref "MD9") (pin "1") (pinfunction "IPROPI_1") (pintype "power_in"))
      (node (ref "R9") (pin "2") (pinfunction "2_2") (pintype "passive"))
      (node (ref "U1") (pin "86") (pinfunction "PD5_86") (pintype "bidirectional"))
    )
    (net (code "54") (name "/IPROPI10") (class "Default")
      (node (ref "MD10") (pin "1") (pinfunction "IPROPI_1") (pintype "power_in"))
      (node (ref "R10") (pin "2") (pinfunction "2_2") (pintype "passive"))
      (node (ref "U1") (pin "85") (pinfunction "PD4_85") (pintype "bidirectional"))
    )
    (net (code "55") (name "/OSC_H_IN") (class "Default")
      (node (ref "C15") (pin "2") (pinfunction "2_2") (pintype "passive"))
      (node (ref "U1") (pin "12") (pinfunction "PH0-OSC_IN_12") (pintype "bidirectional"))
      (node (ref "XTAL2") (pin "3") (pinfunction "3_3") (pintype "passive"))
    )
    (net (code "56") (name "/OSC_H_OUT") (class "Default")
      (node (ref "C14") (pin "1") (pinfunction "1_1") (pintype "passive"))
      (node (ref "U1") (pin "13") (pinfunction "PH1-OSC_OUT_13") (pintype "bidirectional"))
      (node (ref "XTAL2") (pin "1") (pinfunction "1_1") (pintype "passive"))
    )
    (net (code "57") (name "/OSC_L_IN") (class "Default")
      (node (ref "C13") (pin "1") (pinfunction "1_1") (pintype "passive"))
      (node (ref "U1") (pin "8") (pinfunction "PC14-OSC32_IN_8") (pintype "bidirectional"))
      (node (ref "XTAL1") (pin "4") (pinfunction "4_4") (pintype "passive"))
    )
    (net (code "58") (name "/OSC_L_OUT") (class "Default")
      (node (ref "C12") (pin "1") (pinfunction "1_1") (pintype "passive"))
      (node (ref "U1") (pin "9") (pinfunction "PC15-OSC32_OUT_9") (pintype "bidirectional"))
      (node (ref "XTAL1") (pin "1") (pinfunction "1_1") (pintype "passive"))
    )
    (net (code "59") (name "/OUT1A") (class "Default")
      (node (ref "J1") (pin "1") (pinfunction "1_1") (pintype "passive"))
      (node (ref "MD1") (pin "6") (pinfunction "OUT1_6") (pintype "output"))
    )
    (net (code "60") (name "/OUT1B") (class "Default")
      (node (ref "J1") (pin "2") (pinfunction "2_2") (pintype "passive"))
      (node (ref "MD1") (pin "8") (pinfunction "OUT2_8") (pintype "output"))
    )
    (net (code "61") (name "/OUT2A") (class "Default")
      (node (ref "J2") (pin "1") (pinfunction "1_1") (pintype "passive"))
      (node (ref "MD2") (pin "6") (pinfunction "OUT1_6") (pintype "output"))
    )
    (net (code "62") (name "/OUT2B") (class "Default")
      (node (ref "J2") (pin "2") (pinfunction "2_2") (pintype "passive"))
      (node (ref "MD2") (pin "8") (pinfunction "OUT2_8") (pintype "output"))
    )
    (net (code "63") (name "/OUT3A") (class "Default")
      (node (ref "J3") (pin "1") (pinfunction "1_1") (pintype "passive"))
      (node (ref "MD3") (pin "6") (pinfunction "OUT1_6") (pintype "output"))
    )
    (net (code "64") (name "/OUT3B") (class "Default")
      (node (ref "J3") (pin "2") (pinfunction "2_2") (pintype "passive"))
      (node (ref "MD3") (pin "8") (pinfunction "OUT2_8") (pintype "output"))
    )
    (net (code "65") (name "/OUT4A") (class "Default")
      (node (ref "J4") (pin "1") (pinfunction "1_1") (pintype "passive"))
      (node (ref "MD4") (pin "6") (pinfunction "OUT1_6") (pintype "output"))
    )
    (net (code "66") (name "/OUT4B") (class "Default")
      (node (ref "J4") (pin "2") (pinfunction "2_2") (pintype "passive"))
      (node (ref "MD4") (pin "8") (pinfunction "OUT2_8") (pintype "output"))
    )
    (net (code "67") (name "/OUT5A") (class "Default")
      (node (ref "J5") (pin "1") (pinfunction "1_1") (pintype "passive"))
      (node (ref "MD5") (pin "6") (pinfunction "OUT1_6") (pintype "output"))
    )
    (net (code "68") (name "/OUT5B") (class "Default")
      (node (ref "J5") (pin "2") (pinfunction "2_2") (pintype "passive"))
      (node (ref "MD5") (pin "8") (pinfunction "OUT2_8") (pintype "output"))
    )
    (net (code "69") (name "/OUT6A") (class "Default")
      (node (ref "J6") (pin "1") (pinfunction "1_1") (pintype "passive"))
      (node (ref "MD6") (pin "6") (pinfunction "OUT1_6") (pintype "output"))
    )
    (net (code "70") (name "/OUT6B") (class "Default")
      (node (ref "J6") (pin "2") (pinfunction "2_2") (pintype "passive"))
      (node (ref "MD6") (pin "8") (pinfunction "OUT2_8") (pintype "output"))
    )
    (net (code "71") (name "/OUT7A") (class "Default")
      (node (ref "J7") (pin "1") (pinfunction "1_1") (pintype "passive"))
      (node (ref "MD7") (pin "6") (pinfunction "OUT1_6") (pintype "output"))
    )
    (net (code "72") (name "/OUT7B") (class "Default")
      (node (ref "J7") (pin "2") (pinfunction "2_2") (pintype "passive"))
      (node (ref "MD7") (pin "8") (pinfunction "OUT2_8") (pintype "output"))
    )
    (net (code "73") (name "/OUT8A") (class "Default")
      (node (ref "J8") (pin "1") (pinfunction "1_1") (pintype "passive"))
      (node (ref "MD8") (pin "6") (pinfunction "OUT1_6") (pintype "output"))
    )
    (net (code "74") (name "/OUT8B") (class "Default")
      (node (ref "J8") (pin "2") (pinfunction "2_2") (pintype "passive"))
      (node (ref "MD8") (pin "8") (pinfunction "OUT2_8") (pintype "output"))
    )
    (net (code "75") (name "/OUT9A") (class "Default")
      (node (ref "J9") (pin "1") (pinfunction "1_1") (pintype "passive"))
      (node (ref "MD9") (pin "6") (pinfunction "OUT1_6") (pintype "output"))
    )
    (net (code "76") (name "/OUT9B") (class "Default")
      (node (ref "J9") (pin "2") (pinfunction "2_2") (pintype "passive"))
      (node (ref "MD9") (pin "8") (pinfunction "OUT2_8") (pintype "output"))
    )
    (net (code "77") (name "/OUT10A") (class "Default")
      (node (ref "J10") (pin "1") (pinfunction "1_1") (pintype "passive"))
      (node (ref "MD10") (pin "6") (pinfunction "OUT1_6") (pintype "output"))
    )
    (net (code "78") (name "/OUT10B") (class "Default")
      (node (ref "J10") (pin "2") (pinfunction "2_2") (pintype "passive"))
      (node (ref "MD10") (pin "8") (pinfunction "OUT2_8") (pintype "output"))
    )
    (net (code "79") (name "/RESET") (class "Default")
      (node (ref "C11") (pin "2") (pinfunction "2_2") (pintype "passive"))
      (node (ref "J25") (pin "2") (pinfunction "2_2") (pintype "passive"))
      (node (ref "SW1") (pin "1") (pinfunction "1_1") (pintype "passive"))
      (node (ref "U1") (pin "14") (pinfunction "NRST_14") (pintype "bidirectional"))
    )
    (net (code "80") (name "/SWCLK") (class "Default")
      (node (ref "J25") (pin "3") (pinfunction "3_3") (pintype "passive"))
      (node (ref "U1") (pin "76") (pinfunction "PA14_76") (pintype "bidirectional"))
    )
    (net (code "81") (name "/SWDIO") (class "Default")
      (node (ref "J25") (pin "1") (pinfunction "1_1") (pintype "passive"))
      (node (ref "U1") (pin "72") (pinfunction "PA13_72") (pintype "bidirectional"))
    )
    (net (code "82") (name "/SWO") (class "Default")
      (node (ref "J25") (pin "5") (pinfunction "5_5") (pintype "passive"))
      (node (ref "U1") (pin "89") (pinfunction "PB3_89") (pintype "bidirectional"))
    )
    (net (code "83") (name "/TH1") (class "Default")
      (node (ref "J11") (pin "2") (pinfunction "2_2") (pintype "passive"))
      (node (ref "R13") (pin "1") (pinfunction "1_1") (pintype "passive"))
      (node (ref "U1") (pin "23") (pinfunction "PA0_23") (pintype "bidirectional"))
    )
    (net (code "84") (name "/TH2") (class "Default")
      (node (ref "J12") (pin "2") (pinfunction "2_2") (pintype "passive"))
      (node (ref "R14") (pin "1") (pinfunction "1_1") (pintype "passive"))
      (node (ref "U1") (pin "24") (pinfunction "PA1_24") (pintype "bidirectional"))
    )
    (net (code "85") (name "/TH3") (class "Default")
      (node (ref "J13") (pin "2") (pinfunction "2_2") (pintype "passive"))
      (node (ref "R15") (pin "1") (pinfunction "1_1") (pintype "passive"))
      (node (ref "U1") (pin "25") (pinfunction "PA2_25") (pintype "bidirectional"))
    )
    (net (code "86") (name "/TH4") (class "Default")
      (node (ref "J14") (pin "2") (pinfunction "2_2") (pintype "passive"))
      (node (ref "R16") (pin "1") (pinfunction "1_1") (pintype "passive"))
      (node (ref "U1") (pin "26") (pinfunction "PA3_26") (pintype "bidirectional"))
    )
    (net (code "87") (name "/TH5") (class "Default")
      (node (ref "J15") (pin "2") (pinfunction "2_2") (pintype "passive"))
      (node (ref "R17") (pin "1") (pinfunction "1_1") (pintype "passive"))
      (node (ref "U1") (pin "29") (pinfunction "PA4_29") (pintype "bidirectional"))
    )
    (net (code "88") (name "/TH6") (class "Default")
      (node (ref "J16") (pin "2") (pinfunction "2_2") (pintype "passive"))
      (node (ref "R18") (pin "1") (pinfunction "1_1") (pintype "passive"))
      (node (ref "U1") (pin "30") (pinfunction "PA5_30") (pintype "bidirectional"))
    )
    (net (code "89") (name "/TH7") (class "Default")
      (node (ref "J17") (pin "2") (pinfunction "2_2") (pintype "passive"))
      (node (ref "R19") (pin "1") (pinfunction "1_1") (pintype "passive"))
      (node (ref "U1") (pin "31") (pinfunction "PA6_31") (pintype "bidirectional"))
    )
    (net (code "90") (name "/TH8") (class "Default")
      (node (ref "J18") (pin "2") (pinfunction "2_2") (pintype "passive"))
      (node (ref "R20") (pin "1") (pinfunction "1_1") (pintype "passive"))
      (node (ref "U1") (pin "32") (pinfunction "PA7_32") (pintype "bidirectional"))
    )
    (net (code "91") (name "/TH9") (class "Default")
      (node (ref "J19") (pin "2") (pinfunction "2_2") (pintype "passive"))
      (node (ref "R21") (pin "1") (pinfunction "1_1") (pintype "passive"))
      (node (ref "U1") (pin "33") (pinfunction "PC4_33") (pintype "bidirectional"))
    )
    (net (code "92") (name "/TH10") (class "Default")
      (node (ref "J20") (pin "2") (pinfunction "2_2") (pintype "passive"))
      (node (ref "R22") (pin "1") (pinfunction "1_1") (pintype "passive"))
      (node (ref "U1") (pin "34") (pinfunction "PC5_34") (pintype "bidirectional"))
    )
    (net (code "93") (name "3.3V") (class "Default")
      (node (ref "C1") (pin "1") (pinfunction "1_1") (pintype "passive"))
      (node (ref "C10") (pin "2") (pinfunction "2_2") (pintype "passive"))
      (node (ref "C2") (pin "1") (pinfunction "1_1") (pintype "passive"))
      (node (ref "C4") (pin "1") (pinfunction "1_1") (pintype "passive"))
      (node (ref "C5") (pin "1") (pinfunction "1_1") (pintype "passive"))
      (node (ref "C6") (pin "1") (pinfunction "1_1") (pintype "passive"))
      (node (ref "C7") (pin "1") (pinfunction "1_1") (pintype "passive"))
      (node (ref "C8") (pin "1") (pinfunction "1_1") (pintype "passive"))
      (node (ref "C9") (pin "1") (pinfunction "1_1") (pintype "passive"))
      (node (ref "J21") (pin "11") (pinfunction "11_11") (pintype "passive"))
      (node (ref "J22") (pin "11") (pinfunction "11_11") (pintype "passive"))
      (node (ref "J24") (pin "1") (pinfunction "1_1") (pintype "passive"))
      (node (ref "J25") (pin "4") (pinfunction "4_4") (pintype "passive"))
      (node (ref "J26") (pin "4") (pinfunction "4_4") (pintype "passive"))
      (node (ref "MD1") (pin "4") (pinfunction "VREF_4") (pintype "power_in"))
      (node (ref "MD10") (pin "4") (pinfunction "VREF_4") (pintype "power_in"))
      (node (ref "MD2") (pin "4") (pinfunction "VREF_4") (pintype "power_in"))
      (node (ref "MD3") (pin "4") (pinfunction "VREF_4") (pintype "power_in"))
      (node (ref "MD4") (pin "4") (pinfunction "VREF_4") (pintype "power_in"))
      (node (ref "MD5") (pin "4") (pinfunction "VREF_4") (pintype "power_in"))
      (node (ref "MD6") (pin "4") (pinfunction "VREF_4") (pintype "power_in"))
      (node (ref "MD7") (pin "4") (pinfunction "VREF_4") (pintype "power_in"))
      (node (ref "MD8") (pin "4") (pinfunction "VREF_4") (pintype "power_in"))
      (node (ref "MD9") (pin "4") (pinfunction "VREF_4") (pintype "power_in"))
      (node (ref "R13") (pin "2") (pinfunction "2_2") (pintype "passive"))
      (node (ref "R14") (pin "2") (pinfunction "2_2") (pintype "passive"))
      (node (ref "R15") (pin "2") (pinfunction "2_2") (pintype "passive"))
      (node (ref "R16") (pin "2") (pinfunction "2_2") (pintype "passive"))
      (node (ref "R17") (pin "2") (pinfunction "2_2") (pintype "passive"))
      (node (ref "R18") (pin "2") (pinfunction "2_2") (pintype "passive"))
      (node (ref "R19") (pin "2") (pinfunction "2_2") (pintype "passive"))
      (node (ref "R20") (pin "2") (pinfunction "2_2") (pintype "passive"))
      (node (ref "R21") (pin "2") (pinfunction "2_2") (pintype "passive"))
      (node (ref "R22") (pin "2") (pinfunction "2_2") (pintype "passive"))
      (node (ref "U1") (pin "100") (pinfunction "VDD_100") (pintype "power_in"))
      (node (ref "U1") (pin "11") (pinfunction "VDD_11") (pintype "power_in"))
      (node (ref "U1") (pin "21") (pinfunction "VREF+_21") (pintype "power_in"))
      (node (ref "U1") (pin "22") (pinfunction "VDDA_22") (pintype "power_in"))
      (node (ref "U1") (pin "28") (pinfunction "VDD_28") (pintype "power_in"))
      (node (ref "U1") (pin "50") (pinfunction "VDD_50") (pintype "power_in"))
      (node (ref "U1") (pin "6") (pinfunction "VBAT_6") (pintype "power_in"))
      (node (ref "U1") (pin "73") (pinfunction "VDDUSB_73") (pintype "power_in"))
      (node (ref "U1") (pin "75") (pinfunction "VDD_75") (pintype "power_in"))
      (node (ref "U2") (pin "3") (pinfunction "VCC_3") (pintype "power_in"))
    )
    (net (code "94") (name "5V") (class "Default")
      (node (ref "J26") (pin "3") (pinfunction "3_3") (pintype "passive"))
    )
    (net (code "95") (name "12V") (class "Default")
      (node (ref "C18") (pin "1") (pinfunction "1_1") (pintype "passive"))
      (node (ref "C19") (pin "2") (pinfunction "2_2") (pintype "passive"))
      (node (ref "C20") (pin "1") (pinfunction "1_1") (pintype "passive"))
      (node (ref "C21") (pin "2") (pinfunction "2_2") (pintype "passive"))
      (node (ref "C22") (pin "1") (pinfunction "1_1") (pintype "passive"))
      (node (ref "C23") (pin "2") (pinfunction "2_2") (pintype "passive"))
      (node (ref "C24") (pin "1") (pinfunction "1_1") (pintype "passive"))
      (node (ref "C25") (pin "2") (pinfunction "2_2") (pintype "passive"))
      (node (ref "C26") (pin "1") (pinfunction "1_1") (pintype "passive"))
      (node (ref "C27") (pin "2") (pinfunction "2_2") (pintype "passive"))
      (node (ref "C28") (pin "1") (pinfunction "1_1") (pintype "passive"))
      (node (ref "C29") (pin "2") (pinfunction "2_2") (pintype "passive"))
      (node (ref "C30") (pin "1") (pinfunction "1_1") (pintype "passive"))
      (node (ref "C31") (pin "2") (pinfunction "2_2") (pintype "passive"))
      (node (ref "C32") (pin "1") (pinfunction "1_1") (pintype "passive"))
      (node (ref "C33") (pin "2") (pinfunction "2_2") (pintype "passive"))
      (node (ref "C34") (pin "1") (pinfunction "1_1") (pintype "passive"))
      (node (ref "C35") (pin "2") (pinfunction "2_2") (pintype "passive"))
      (node (ref "C36") (pin "1") (pinfunction "1_1") (pintype "passive"))
      (node (ref "C37") (pin "2") (pinfunction "2_2") (pintype "passive"))
      (node (ref "J23") (pin "2") (pinfunction "2_2") (pintype "passive"))
      (node (ref "MD1") (pin "5") (pinfunction "VM_5") (pintype "power_in"))
      (node (ref "MD10") (pin "5") (pinfunction "VM_5") (pintype "power_in"))
      (node (ref "MD2") (pin "5") (pinfunction "VM_5") (pintype "power_in"))
      (node (ref "MD3") (pin "5") (pinfunction "VM_5") (pintype "power_in"))
      (node (ref "MD4") (pin "5") (pinfunction "VM_5") (pintype "power_in"))
      (node (ref "MD5") (pin "5") (pinfunction "VM_5") (pintype "power_in"))
      (node (ref "MD6") (pin "5") (pinfunction "VM_5") (pintype "power_in"))
      (node (ref "MD7") (pin "5") (pinfunction "VM_5") (pintype "power_in"))
      (node (ref "MD8") (pin "5") (pinfunction "VM_5") (pintype "power_in"))
      (node (ref "MD9") (pin "5") (pinfunction "VM_5") (pintype "power_in"))
    )
    (net (code "96") (name "12Va") (class "Default")
      (node (ref "J26") (pin "5") (pinfunction "5_5") (pintype "passive"))
    )
    (net (code "97") (name "GND") (class "Default")
      (node (ref "C1") (pin "2") (pinfunction "2_2") (pintype "passive"))
      (node (ref "C10") (pin "1") (pinfunction "1_1") (pintype "passive"))
      (node (ref "C11") (pin "1") (pinfunction "1_1") (pintype "passive"))
      (node (ref "C12") (pin "2") (pinfunction "2_2") (pintype "passive"))
      (node (ref "C13") (pin "2") (pinfunction "2_2") (pintype "passive"))
      (node (ref "C14") (pin "2") (pinfunction "2_2") (pintype "passive"))
      (node (ref "C15") (pin "1") (pinfunction "1_1") (pintype "passive"))
      (node (ref "C16") (pin "2") (pinfunction "2_2") (pintype "passive"))
      (node (ref "C17") (pin "2") (pinfunction "2_2") (pintype "passive"))
      (node (ref "C18") (pin "2") (pinfunction "2_2") (pintype "passive"))
      (node (ref "C19") (pin "1") (pinfunction "1_1") (pintype "passive"))
      (node (ref "C2") (pin "2") (pinfunction "2_2") (pintype "passive"))
      (node (ref "C20") (pin "2") (pinfunction "2_2") (pintype "passive"))
      (node (ref "C21") (pin "1") (pinfunction "1_1") (pintype "passive"))
      (node (ref "C22") (pin "2") (pinfunction "2_2") (pintype "passive"))
      (node (ref "C23") (pin "1") (pinfunction "1_1") (pintype "passive"))
      (node (ref "C24") (pin "2") (pinfunction "2_2") (pintype "passive"))
      (node (ref "C25") (pin "1") (pinfunction "1_1") (pintype "passive"))
      (node (ref "C26") (pin "2") (pinfunction "2_2") (pintype "passive"))
      (node (ref "C27") (pin "1") (pinfunction "1_1") (pintype "passive"))
      (node (ref "C28") (pin "2") (pinfunction "2_2") (pintype "passive"))
      (node (ref "C29") (pin "1") (pinfunction "1_1") (pintype "passive"))
      (node (ref "C3") (pin "2") (pinfunction "2_2") (pintype "passive"))
      (node (ref "C30") (pin "2") (pinfunction "2_2") (pintype "passive"))
      (node (ref "C31") (pin "1") (pinfunction "1_1") (pintype "passive"))
      (node (ref "C32") (pin "2") (pinfunction "2_2") (pintype "passive"))
      (node (ref "C33") (pin "1") (pinfunction "1_1") (pintype "passive"))
      (node (ref "C34") (pin "2") (pinfunction "2_2") (pintype "passive"))
      (node (ref "C35") (pin "1") (pinfunction "1_1") (pintype "passive"))
      (node (ref "C36") (pin "2") (pinfunction "2_2") (pintype "passive"))
      (node (ref "C37") (pin "1") (pinfunction "1_1") (pintype "passive"))
      (node (ref "C4") (pin "2") (pinfunction "2_2") (pintype "passive"))
      (node (ref "C5") (pin "2") (pinfunction "2_2") (pintype "passive"))
      (node (ref "C6") (pin "2") (pinfunction "2_2") (pintype "passive"))
      (node (ref "C7") (pin "2") (pinfunction "2_2") (pintype "passive"))
      (node (ref "C8") (pin "2") (pinfunction "2_2") (pintype "passive"))
      (node (ref "C9") (pin "2") (pinfunction "2_2") (pintype "passive"))
      (node (ref "J11") (pin "1") (pinfunction "1_1") (pintype "passive"))
      (node (ref "J12") (pin "1") (pinfunction "1_1") (pintype "passive"))
      (node (ref "J13") (pin "1") (pinfunction "1_1") (pintype "passive"))
      (node (ref "J14") (pin "1") (pinfunction "1_1") (pintype "passive"))
      (node (ref "J15") (pin "1") (pinfunction "1_1") (pintype "passive"))
      (node (ref "J16") (pin "1") (pinfunction "1_1") (pintype "passive"))
      (node (ref "J17") (pin "1") (pinfunction "1_1") (pintype "passive"))
      (node (ref "J18") (pin "1") (pinfunction "1_1") (pintype "passive"))
      (node (ref "J19") (pin "1") (pinfunction "1_1") (pintype "passive"))
      (node (ref "J20") (pin "1") (pinfunction "1_1") (pintype "passive"))
      (node (ref "J23") (pin "1") (pinfunction "1_1") (pintype "passive"))
      (node (ref "J24") (pin "2") (pinfunction "2_2") (pintype "passive"))
      (node (ref "J25") (pin "6") (pinfunction "6_6") (pintype "passive"))
      (node (ref "J26") (pin "6") (pinfunction "6_6") (pintype "passive"))
      (node (ref "MD1") (pin "7") (pinfunction "GND_7") (pintype "power_in"))
      (node (ref "MD1") (pin "EPAD") (pinfunction "GND_EPAD") (pintype "power_in"))
      (node (ref "MD10") (pin "7") (pinfunction "GND_7") (pintype "power_in"))
      (node (ref "MD10") (pin "EPAD") (pinfunction "GND_EPAD") (pintype "power_in"))
      (node (ref "MD2") (pin "7") (pinfunction "GND_7") (pintype "power_in"))
      (node (ref "MD2") (pin "EPAD") (pinfunction "GND_EPAD") (pintype "power_in"))
      (node (ref "MD3") (pin "7") (pinfunction "GND_7") (pintype "power_in"))
      (node (ref "MD3") (pin "EPAD") (pinfunction "GND_EPAD") (pintype "power_in"))
      (node (ref "MD4") (pin "7") (pinfunction "GND_7") (pintype "power_in"))
      (node (ref "MD4") (pin "EPAD") (pinfunction "GND_EPAD") (pintype "power_in"))
      (node (ref "MD5") (pin "7") (pinfunction "GND_7") (pintype "power_in"))
      (node (ref "MD5") (pin "EPAD") (pinfunction "GND_EPAD") (pintype "power_in"))
      (node (ref "MD6") (pin "7") (pinfunction "GND_7") (pintype "power_in"))
      (node (ref "MD6") (pin "EPAD") (pinfunction "GND_EPAD") (pintype "power_in"))
      (node (ref "MD7") (pin "7") (pinfunction "GND_7") (pintype "power_in"))
      (node (ref "MD7") (pin "EPAD") (pinfunction "GND_EPAD") (pintype "power_in"))
      (node (ref "MD8") (pin "7") (pinfunction "GND_7") (pintype "power_in"))
      (node (ref "MD8") (pin "EPAD") (pinfunction "GND_EPAD") (pintype "power_in"))
      (node (ref "MD9") (pin "7") (pinfunction "GND_7") (pintype "power_in"))
      (node (ref "MD9") (pin "EPAD") (pinfunction "GND_EPAD") (pintype "power_in"))
      (node (ref "R1") (pin "1") (pinfunction "1_1") (pintype "passive"))
      (node (ref "R10") (pin "1") (pinfunction "1_1") (pintype "passive"))
      (node (ref "R2") (pin "1") (pinfunction "1_1") (pintype "passive"))
      (node (ref "R3") (pin "1") (pinfunction "1_1") (pintype "passive"))
      (node (ref "R4") (pin "1") (pinfunction "1_1") (pintype "passive"))
      (node (ref "R5") (pin "1") (pinfunction "1_1") (pintype "passive"))
      (node (ref "R6") (pin "1") (pinfunction "1_1") (pintype "passive"))
      (node (ref "R7") (pin "1") (pinfunction "1_1") (pintype "passive"))
      (node (ref "R8") (pin "1") (pinfunction "1_1") (pintype "passive"))
      (node (ref "R9") (pin "1") (pinfunction "1_1") (pintype "passive"))
      (node (ref "SW1") (pin "2") (pinfunction "2_2") (pintype "passive"))
      (node (ref "U1") (pin "10") (pinfunction "VSS_10") (pintype "power_in"))
      (node (ref "U1") (pin "19") (pinfunction "VSSA_19") (pintype "power_in"))
      (node (ref "U1") (pin "20") (pinfunction "VREF-_20") (pintype "power_in"))
      (node (ref "U1") (pin "27") (pinfunction "VSS_27") (pintype "power_in"))
      (node (ref "U1") (pin "49") (pinfunction "VSS_49") (pintype "power_in"))
      (node (ref "U1") (pin "74") (pinfunction "VSS_74") (pintype "power_in"))
      (node (ref "U1") (pin "94") (pinfunction "BOOT0_94") (pintype "input"))
      (node (ref "U1") (pin "99") (pinfunction "VSS_99") (pintype "power_in"))
      (node (ref "U2") (pin "2") (pinfunction "GND_2") (pintype "power_in"))
      (node (ref "U2") (pin "5") (pinfunction "SHDN_5") (pintype "input"))
      (node (ref "U2") (pin "8") (pinfunction "STB_8") (pintype "input"))
      (node (ref "XTAL1") (pin "2") (pinfunction "2_2") (pintype "passive"))
      (node (ref "XTAL1") (pin "3") (pinfunction "3_3") (pintype "passive"))
      (node (ref "XTAL2") (pin "2") (pinfunction "GND_2") (pintype "power_in"))
      (node (ref "XTAL2") (pin "4") (pinfunction "GND_4") (pintype "power_in"))
    )
    (net (code "98") (name "Net-(C3-Pad1)") (class "Default")
      (node (ref "C3") (pin "1") (pinfunction "1_1") (pintype "passive"))
      (node (ref "R11") (pin "1") (pinfunction "1_1") (pintype "passive"))
      (node (ref "R12") (pin "2") (pinfunction "2_2") (pintype "passive"))
    )
    (net (code "99") (name "Net-(C16-Pad1)") (class "Default")
      (node (ref "C16") (pin "1") (pinfunction "1_1") (pintype "passive"))
      (node (ref "U1") (pin "48") (pinfunction "VCAP_48") (pintype "power_in"))
    )
    (net (code "100") (name "Net-(C17-Pad1)") (class "Default")
      (node (ref "C17") (pin "1") (pinfunction "1_1") (pintype "passive"))
      (node (ref "U1") (pin "98") (pinfunction "VCAP_98") (pintype "power_in"))
    )
    (net (code "101") (name "unconnected-(J11-PadMP1)") (class "Default")
      (node (ref "J11") (pin "MP1") (pinfunction "MP1_MP1") (pintype "passive"))
    )
    (net (code "102") (name "unconnected-(J11-PadMP2)") (class "Default")
      (node (ref "J11") (pin "MP2") (pinfunction "MP2_MP2") (pintype "passive"))
    )
    (net (code "103") (name "unconnected-(J12-PadMP1)") (class "Default")
      (node (ref "J12") (pin "MP1") (pinfunction "MP1_MP1") (pintype "passive"))
    )
    (net (code "104") (name "unconnected-(J12-PadMP2)") (class "Default")
      (node (ref "J12") (pin "MP2") (pinfunction "MP2_MP2") (pintype "passive"))
    )
    (net (code "105") (name "unconnected-(J13-PadMP1)") (class "Default")
      (node (ref "J13") (pin "MP1") (pinfunction "MP1_MP1") (pintype "passive"))
    )
    (net (code "106") (name "unconnected-(J13-PadMP2)") (class "Default")
      (node (ref "J13") (pin "MP2") (pinfunction "MP2_MP2") (pintype "passive"))
    )
    (net (code "107") (name "unconnected-(J14-PadMP1)") (class "Default")
      (node (ref "J14") (pin "MP1") (pinfunction "MP1_MP1") (pintype "passive"))
    )
    (net (code "108") (name "unconnected-(J14-PadMP2)") (class "Default")
      (node (ref "J14") (pin "MP2") (pinfunction "MP2_MP2") (pintype "passive"))
    )
    (net (code "109") (name "unconnected-(J15-PadMP1)") (class "Default")
      (node (ref "J15") (pin "MP1") (pinfunction "MP1_MP1") (pintype "passive"))
    )
    (net (code "110") (name "unconnected-(J15-PadMP2)") (class "Default")
      (node (ref "J15") (pin "MP2") (pinfunction "MP2_MP2") (pintype "passive"))
    )
    (net (code "111") (name "unconnected-(J16-PadMP1)") (class "Default")
      (node (ref "J16") (pin "MP1") (pinfunction "MP1_MP1") (pintype "passive"))
    )
    (net (code "112") (name "unconnected-(J16-PadMP2)") (class "Default")
      (node (ref "J16") (pin "MP2") (pinfunction "MP2_MP2") (pintype "passive"))
    )
    (net (code "113") (name "unconnected-(J17-PadMP1)") (class "Default")
      (node (ref "J17") (pin "MP1") (pinfunction "MP1_MP1") (pintype "passive"))
    )
    (net (code "114") (name "unconnected-(J17-PadMP2)") (class "Default")
      (node (ref "J17") (pin "MP2") (pinfunction "MP2_MP2") (pintype "passive"))
    )
    (net (code "115") (name "unconnected-(J18-PadMP1)") (class "Default")
      (node (ref "J18") (pin "MP1") (pinfunction "MP1_MP1") (pintype "passive"))
    )
    (net (code "116") (name "unconnected-(J18-PadMP2)") (class "Default")
      (node (ref "J18") (pin "MP2") (pinfunction "MP2_MP2") (pintype "passive"))
    )
    (net (code "117") (name "unconnected-(J19-PadMP1)") (class "Default")
      (node (ref "J19") (pin "MP1") (pinfunction "MP1_MP1") (pintype "passive"))
    )
    (net (code "118") (name "unconnected-(J19-PadMP2)") (class "Default")
      (node (ref "J19") (pin "MP2") (pinfunction "MP2_MP2") (pintype "passive"))
    )
    (net (code "119") (name "unconnected-(J20-PadMP1)") (class "Default")
      (node (ref "J20") (pin "MP1") (pinfunction "MP1_MP1") (pintype "passive"))
    )
    (net (code "120") (name "unconnected-(J20-PadMP2)") (class "Default")
      (node (ref "J20") (pin "MP2") (pinfunction "MP2_MP2") (pintype "passive"))
    )
    (net (code "121") (name "unconnected-(U1A-PC0-Pad15)") (class "Default")
      (node (ref "U1") (pin "15") (pinfunction "PC0_15") (pintype "bidirectional+no_connect"))
    )
    (net (code "122") (name "unconnected-(U1A-PC1-Pad16)") (class "Default")
      (node (ref "U1") (pin "16") (pinfunction "PC1_16") (pintype "bidirectional+no_connect"))
    )
    (net (code "123") (name "unconnected-(U1A-PC2-Pad17)") (class "Default")
      (node (ref "U1") (pin "17") (pinfunction "PC2_17") (pintype "bidirectional+no_connect"))
    )
    (net (code "124") (name "unconnected-(U1A-PC3-Pad18)") (class "Default")
      (node (ref "U1") (pin "18") (pinfunction "PC3_18") (pintype "bidirectional+no_connect"))
    )
    (net (code "125") (name "unconnected-(U1A-PC13-Pad7)") (class "Default")
      (node (ref "U1") (pin "7") (pinfunction "PC13_7") (pintype "bidirectional+no_connect"))
    )
    (net (code "126") (name "unconnected-(U1B-PE0-Pad97)") (class "Default")
      (node (ref "U1") (pin "97") (pinfunction "PE0_97") (pintype "bidirectional+no_connect"))
    )
    (net (code "127") (name "unconnected-(U1B-PE2-Pad1)") (class "Default")
      (node (ref "U1") (pin "1") (pinfunction "PE2_1") (pintype "bidirectional+no_connect"))
    )
    (net (code "128") (name "unconnected-(U1B-PE3-Pad2)") (class "Default")
      (node (ref "U1") (pin "2") (pinfunction "PE3_2") (pintype "bidirectional+no_connect"))
    )
    (net (code "129") (name "unconnected-(U1B-PE4-Pad3)") (class "Default")
      (node (ref "U1") (pin "3") (pinfunction "PE4_3") (pintype "bidirectional+no_connect"))
    )
    (net (code "130") (name "unconnected-(U1B-PE5-Pad4)") (class "Default")
      (node (ref "U1") (pin "4") (pinfunction "PE5_4") (pintype "bidirectional+no_connect"))
    )
    (net (code "131") (name "unconnected-(U1B-PE6-Pad5)") (class "Default")
      (node (ref "U1") (pin "5") (pinfunction "PE6_5") (pintype "bidirectional+no_connect"))
    )
  )
)
